# 06_-_LEDs.net
KiCad netlist of a schematic drawn in Altium Designer
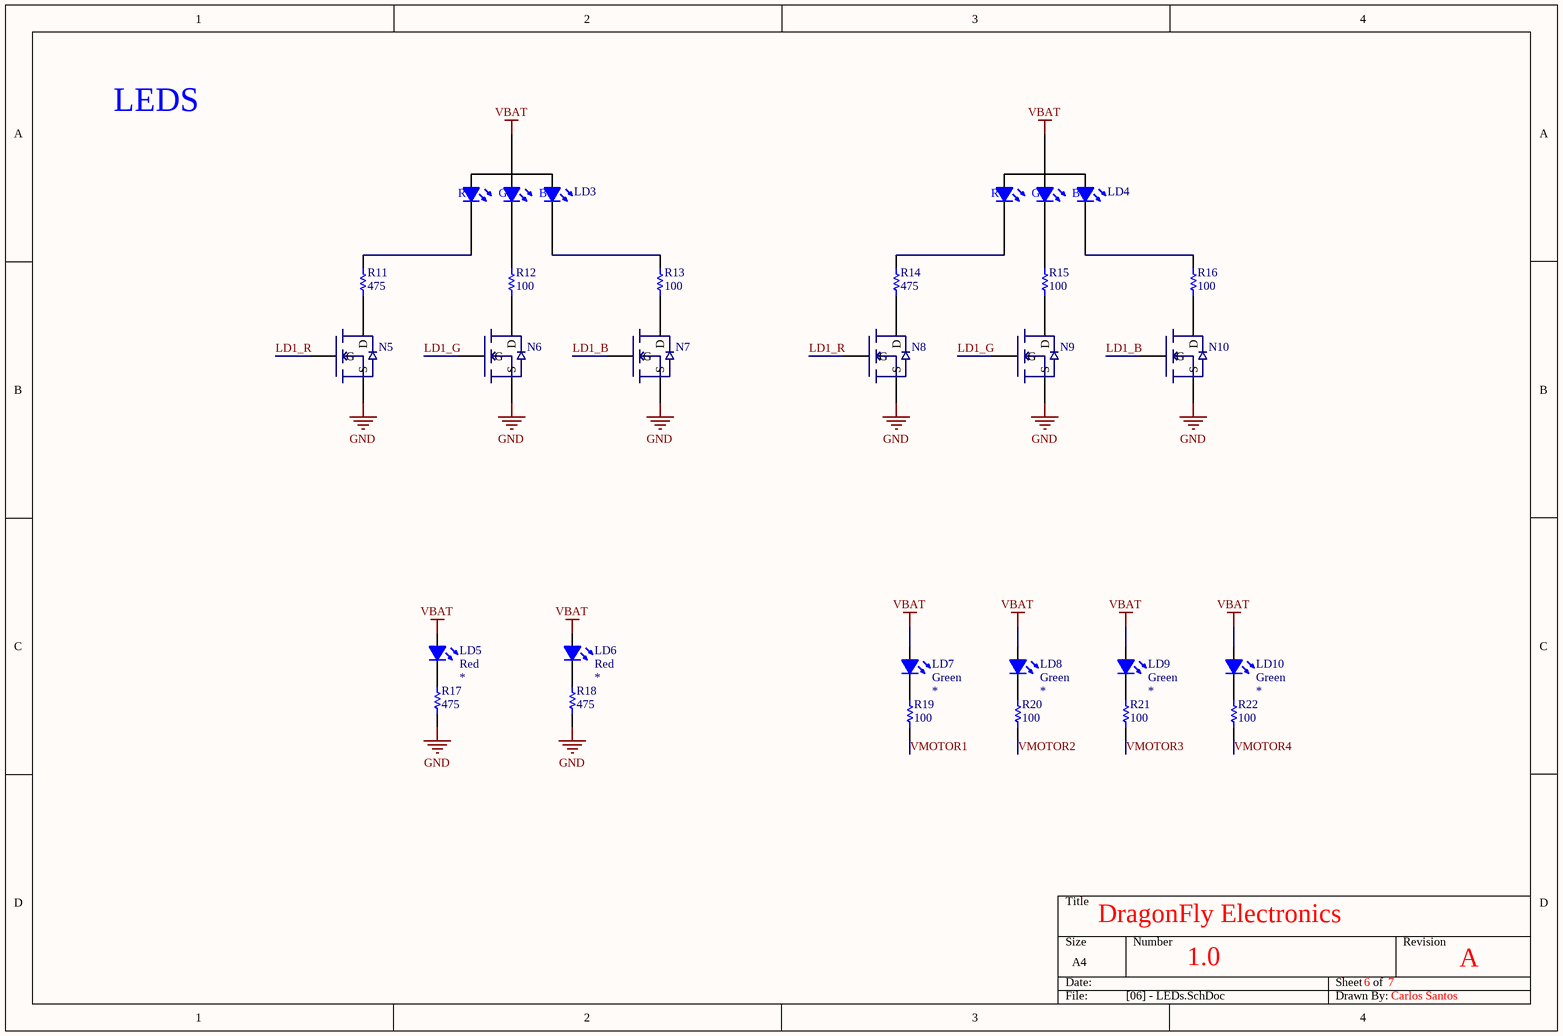
[diagram p0: [06] - LEDs.SchDoc]

(export (version "E")
  (design (tool "Eeschema 10.0.6"))
  (components
    (comp (ref "LD3")
      (value "1")
      (footprint "0404 RGD Led")
      (fields (field (name "DIGIKEY PART #") "475-3597-1-ND"))
      (libsource (lib "Mine") (part "RGB LED"))
    )
    (comp (ref "LD4")
      (value "1")
      (footprint "0404 RGD Led")
      (fields (field (name "DIGIKEY PART #") "475-3597-1-ND"))
      (libsource (lib "Mine") (part "RGB LED"))
    )
    (comp (ref "LD5")
      (value "Led")
      (footprint "0603 - led")
      (fields (field (name "COLOR") "Red") (field (name "VF") "*"))
      (libsource (lib "Mine") (part "Led"))
    )
    (comp (ref "LD6")
      (value "Led")
      (footprint "0603 - led")
      (fields (field (name "COLOR") "Red") (field (name "VF") "*"))
      (libsource (lib "Mine") (part "Led"))
    )
    (comp (ref "LD7")
      (value "Led")
      (footprint "0603 - led")
      (fields (field (name "COLOR") "Green") (field (name "VF") "*"))
      (libsource (lib "Mine") (part "Led"))
    )
    (comp (ref "LD8")
      (value "Led")
      (footprint "0603 - led")
      (fields (field (name "COLOR") "Green") (field (name "VF") "*"))
      (libsource (lib "Mine") (part "Led"))
    )
    (comp (ref "LD9")
      (value "Led")
      (footprint "0603 - led")
      (fields (field (name "COLOR") "Green") (field (name "VF") "*"))
      (libsource (lib "Mine") (part "Led"))
    )
    (comp (ref "LD10")
      (value "Led")
      (footprint "0603 - led")
      (fields (field (name "COLOR") "Green") (field (name "VF") "*"))
      (libsource (lib "Mine") (part "Led"))
    )
    (comp (ref "N5") (value "N-MOSFET") (footprint "DFN1006-3") (libsource (lib "Mine") (part "N-MOSFET")))
    (comp (ref "N6") (value "N-MOSFET") (footprint "DFN1006-3") (libsource (lib "Mine") (part "N-MOSFET")))
    (comp (ref "N7") (value "N-MOSFET") (footprint "DFN1006-3") (libsource (lib "Mine") (part "N-MOSFET")))
    (comp (ref "N8") (value "N-MOSFET") (footprint "DFN1006-3") (libsource (lib "Mine") (part "N-MOSFET")))
    (comp (ref "N9") (value "N-MOSFET") (footprint "DFN1006-3") (libsource (lib "Mine") (part "N-MOSFET")))
    (comp (ref "N10") (value "N-MOSFET") (footprint "DFN1006-3") (libsource (lib "Mine") (part "N-MOSFET")))
    (comp (ref "R11")
      (value "475")
      (footprint "0402 - Resistor")
      (fields (field (name "Comment") "Resistor"))
      (libsource (lib "Mine") (part "Resistor"))
    )
    (comp (ref "R12")
      (value "100")
      (footprint "0402 - Resistor")
      (fields (field (name "Comment") "Resistor"))
      (libsource (lib "Mine") (part "Resistor"))
    )
    (comp (ref "R13")
      (value "100")
      (footprint "0402 - Resistor")
      (fields (field (name "Comment") "Resistor"))
      (libsource (lib "Mine") (part "Resistor"))
    )
    (comp (ref "R14")
      (value "475")
      (footprint "0402 - Resistor")
      (fields (field (name "Comment") "Resistor"))
      (libsource (lib "Mine") (part "Resistor"))
    )
    (comp (ref "R15")
      (value "100")
      (footprint "0402 - Resistor")
      (fields (field (name "Comment") "Resistor"))
      (libsource (lib "Mine") (part "Resistor"))
    )
    (comp (ref "R16")
      (value "100")
      (footprint "0402 - Resistor")
      (fields (field (name "Comment") "Resistor"))
      (libsource (lib "Mine") (part "Resistor"))
    )
    (comp (ref "R17")
      (value "475")
      (footprint "0402 - Resistor")
      (fields (field (name "Comment") "Resistor"))
      (libsource (lib "Mine") (part "Resistor"))
    )
    (comp (ref "R18")
      (value "475")
      (footprint "0402 - Resistor")
      (fields (field (name "Comment") "Resistor"))
      (libsource (lib "Mine") (part "Resistor"))
    )
    (comp (ref "R19")
      (value "100")
      (footprint "0402 - Resistor")
      (fields (field (name "Comment") "Resistor"))
      (libsource (lib "Mine") (part "Resistor"))
    )
    (comp (ref "R20")
      (value "100")
      (footprint "0402 - Resistor")
      (fields (field (name "Comment") "Resistor"))
      (libsource (lib "Mine") (part "Resistor"))
    )
    (comp (ref "R21")
      (value "100")
      (footprint "0402 - Resistor")
      (fields (field (name "Comment") "Resistor"))
      (libsource (lib "Mine") (part "Resistor"))
    )
    (comp (ref "R22")
      (value "100")
      (footprint "0402 - Resistor")
      (fields (field (name "Comment") "Resistor"))
      (libsource (lib "Mine") (part "Resistor"))
    )
  )
  (nets
    (net (code "1") (name "/LD1_B") (class "Default")
      (node (ref "N10") (pin "2") (pinfunction "G_2") (pintype "passive"))
      (node (ref "N7") (pin "2") (pinfunction "G_2") (pintype "passive"))
    )
    (net (code "2") (name "/LD1_G") (class "Default")
      (node (ref "N6") (pin "2") (pinfunction "G_2") (pintype "passive"))
      (node (ref "N9") (pin "2") (pinfunction "G_2") (pintype "passive"))
    )
    (net (code "3") (name "/LD1_R") (class "Default")
      (node (ref "N5") (pin "2") (pinfunction "G_2") (pintype "passive"))
      (node (ref "N8") (pin "2") (pinfunction "G_2") (pintype "passive"))
    )
    (net (code "4") (name "/VMOTOR1") (class "Default")
      (node (ref "R19") (pin "1") (pinfunction "1_1") (pintype "passive"))
    )
    (net (code "5") (name "/VMOTOR2") (class "Default")
      (node (ref "R20") (pin "1") (pinfunction "1_1") (pintype "passive"))
    )
    (net (code "6") (name "/VMOTOR3") (class "Default")
      (node (ref "R21") (pin "1") (pinfunction "1_1") (pintype "passive"))
    )
    (net (code "7") (name "/VMOTOR4") (class "Default")
      (node (ref "R22") (pin "1") (pinfunction "1_1") (pintype "passive"))
    )
    (net (code "8") (name "GND") (class "Default")
      (node (ref "N10") (pin "1") (pinfunction "S_1") (pintype "passive"))
      (node (ref "N5") (pin "1") (pinfunction "S_1") (pintype "passive"))
      (node (ref "N6") (pin "1") (pinfunction "S_1") (pintype "passive"))
      (node (ref "N7") (pin "1") (pinfunction "S_1") (pintype "passive"))
      (node (ref "N8") (pin "1") (pinfunction "S_1") (pintype "passive"))
      (node (ref "N9") (pin "1") (pinfunction "S_1") (pintype "passive"))
      (node (ref "R17") (pin "1") (pinfunction "1_1") (pintype "passive"))
      (node (ref "R18") (pin "1") (pinfunction "1_1") (pintype "passive"))
    )
    (net (code "9") (name "Net-(LD3-Pad2)") (class "Default")
      (node (ref "LD3") (pin "2") (pinfunction "2_2") (pintype "passive"))
      (node (ref "R11") (pin "2") (pinfunction "2_2") (pintype "passive"))
    )
    (net (code "10") (name "Net-(LD3-Pad3)") (class "Default")
      (node (ref "LD3") (pin "3") (pinfunction "3_3") (pintype "passive"))
      (node (ref "R12") (pin "2") (pinfunction "2_2") (pintype "passive"))
    )
    (net (code "11") (name "Net-(LD3-Pad4)") (class "Default")
      (node (ref "LD3") (pin "4") (pinfunction "4_4") (pintype "passive"))
      (node (ref "R13") (pin "2") (pinfunction "2_2") (pintype "passive"))
    )
    (net (code "12") (name "Net-(LD4-Pad2)") (class "Default")
      (node (ref "LD4") (pin "2") (pinfunction "2_2") (pintype "passive"))
      (node (ref "R14") (pin "2") (pinfunction "2_2") (pintype "passive"))
    )
    (net (code "13") (name "Net-(LD4-Pad3)") (class "Default")
      (node (ref "LD4") (pin "3") (pinfunction "3_3") (pintype "passive"))
      (node (ref "R15") (pin "2") (pinfunction "2_2") (pintype "passive"))
    )
    (net (code "14") (name "Net-(LD4-Pad4)") (class "Default")
      (node (ref "LD4") (pin "4") (pinfunction "4_4") (pintype "passive"))
      (node (ref "R16") (pin "2") (pinfunction "2_2") (pintype "passive"))
    )
    (net (code "15") (name "Net-(LD5-K)") (class "Default")
      (node (ref "LD5") (pin "2") (pinfunction "K_2") (pintype "passive"))
      (node (ref "R17") (pin "2") (pinfunction "2_2") (pintype "passive"))
    )
    (net (code "16") (name "Net-(LD6-K)") (class "Default")
      (node (ref "LD6") (pin "2") (pinfunction "K_2") (pintype "passive"))
      (node (ref "R18") (pin "2") (pinfunction "2_2") (pintype "passive"))
    )
    (net (code "17") (name "Net-(LD7-K)") (class "Default")
      (node (ref "LD7") (pin "2") (pinfunction "K_2") (pintype "passive"))
      (node (ref "R19") (pin "2") (pinfunction "2_2") (pintype "passive"))
    )
    (net (code "18") (name "Net-(LD8-K)") (class "Default")
      (node (ref "LD8") (pin "2") (pinfunction "K_2") (pintype "passive"))
      (node (ref "R20") (pin "2") (pinfunction "2_2") (pintype "passive"))
    )
    (net (code "19") (name "Net-(LD9-K)") (class "Default")
      (node (ref "LD9") (pin "2") (pinfunction "K_2") (pintype "passive"))
      (node (ref "R21") (pin "2") (pinfunction "2_2") (pintype "passive"))
    )
    (net (code "20") (name "Net-(LD10-K)") (class "Default")
      (node (ref "LD10") (pin "2") (pinfunction "K_2") (pintype "passive"))
      (node (ref "R22") (pin "2") (pinfunction "2_2") (pintype "passive"))
    )
    (net (code "21") (name "Net-(N5-D)") (class "Default")
      (node (ref "N5") (pin "3") (pinfunction "D_3") (pintype "passive"))
      (node (ref "R11") (pin "1") (pinfunction "1_1") (pintype "passive"))
    )
    (net (code "22") (name "Net-(N6-D)") (class "Default")
      (node (ref "N6") (pin "3") (pinfunction "D_3") (pintype "passive"))
      (node (ref "R12") (pin "1") (pinfunction "1_1") (pintype "passive"))
    )
    (net (code "23") (name "Net-(N7-D)") (class "Default")
      (node (ref "N7") (pin "3") (pinfunction "D_3") (pintype "passive"))
      (node (ref "R13") (pin "1") (pinfunction "1_1") (pintype "passive"))
    )
    (net (code "24") (name "Net-(N8-D)") (class "Default")
      (node (ref "N8") (pin "3") (pinfunction "D_3") (pintype "passive"))
      (node (ref "R14") (pin "1") (pinfunction "1_1") (pintype "passive"))
    )
    (net (code "25") (name "Net-(N9-D)") (class "Default")
      (node (ref "N9") (pin "3") (pinfunction "D_3") (pintype "passive"))
      (node (ref "R15") (pin "1") (pinfunction "1_1") (pintype "passive"))
    )
    (net (code "26") (name "Net-(N10-D)") (class "Default")
      (node (ref "N10") (pin "3") (pinfunction "D_3") (pintype "passive"))
      (node (ref "R16") (pin "1") (pinfunction "1_1") (pintype "passive"))
    )
    (net (code "27") (name "VBAT") (class "Default")
      (node (ref "LD10") (pin "1") (pinfunction "A_1") (pintype "passive"))
      (node (ref "LD3") (pin "1") (pinfunction "1_1") (pintype "passive"))
      (node (ref "LD4") (pin "1") (pinfunction "1_1") (pintype "passive"))
      (node (ref "LD5") (pin "1") (pinfunction "A_1") (pintype "passive"))
      (node (ref "LD6") (pin "1") (pinfunction "A_1") (pintype "passive"))
      (node (ref "LD7") (pin "1") (pinfunction "A_1") (pintype "passive"))
      (node (ref "LD8") (pin "1") (pinfunction "A_1") (pintype "passive"))
      (node (ref "LD9") (pin "1") (pinfunction "A_1") (pintype "passive"))
    )
    (net (code "28") (name "unconnected-(LD3-A-Pad1)") (class "Default")
      (node (ref "LD3") (pin "1") (pinfunction "A_1") (pintype "passive"))
    )
    (net (code "29") (name "unconnected-(LD3-A-Pad1)_1") (class "Default")
      (node (ref "LD3") (pin "1") (pinfunction "A_1") (pintype "passive"))
    )
    (net (code "30") (name "unconnected-(LD3-A-Pad1)_2") (class "Default")
      (node (ref "LD3") (pin "1") (pinfunction "A_1") (pintype "passive"))
    )
    (net (code "31") (name "unconnected-(LD3-K-Pad2)") (class "Default")
      (node (ref "LD3") (pin "2") (pinfunction "K_2") (pintype "passive"))
    )
    (net (code "32") (name "unconnected-(LD3-K-Pad2)_1") (class "Default")
      (node (ref "LD3") (pin "2") (pinfunction "K_2") (pintype "passive"))
    )
    (net (code "33") (name "unconnected-(LD3-K-Pad2)_2") (class "Default")
      (node (ref "LD3") (pin "2") (pinfunction "K_2") (pintype "passive"))
    )
    (net (code "34") (name "unconnected-(LD4-A-Pad1)") (class "Default")
      (node (ref "LD4") (pin "1") (pinfunction "A_1") (pintype "passive"))
    )
    (net (code "35") (name "unconnected-(LD4-A-Pad1)_1") (class "Default")
      (node (ref "LD4") (pin "1") (pinfunction "A_1") (pintype "passive"))
    )
    (net (code "36") (name "unconnected-(LD4-A-Pad1)_2") (class "Default")
      (node (ref "LD4") (pin "1") (pinfunction "A_1") (pintype "passive"))
    )
    (net (code "37") (name "unconnected-(LD4-K-Pad2)") (class "Default")
      (node (ref "LD4") (pin "2") (pinfunction "K_2") (pintype "passive"))
    )
    (net (code "38") (name "unconnected-(LD4-K-Pad2)_1") (class "Default")
      (node (ref "LD4") (pin "2") (pinfunction "K_2") (pintype "passive"))
    )
    (net (code "39") (name "unconnected-(LD4-K-Pad2)_2") (class "Default")
      (node (ref "LD4") (pin "2") (pinfunction "K_2") (pintype "passive"))
    )
  )
)
